# LED_Board_V2.net
KiCad netlist of a schematic drawn in EAGLE
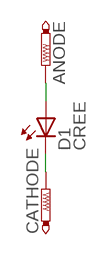
[diagram p0: schematic, sheet 1]

(export (version "E")
  (design (tool "Eeschema 10.0.6"))
  (components
    (comp (ref "ANODE")
      (value "PTR1PAD1-20")
      (footprint "eagle-import:P1-20")
      (libsource (lib "eagle-import") (part "PTR1PAD1-20"))
    )
    (comp (ref "CATHODE")
      (value "PTR1PAD1-20")
      (footprint "eagle-import:P1-20")
      (libsource (lib "eagle-import") (part "PTR1PAD1-20"))
    )
    (comp (ref "D1")
      (value "CREE")
      (footprint "eagle-import:CREE-XLAMP-XM-L")
      (libsource (lib "eagle-import") (part "CREE"))
    )
  )
  (nets
    (net (code "1") (name "Net-(ANODE-PadTP)") (class "Default")
      (node (ref "ANODE") (pin "TP") (pinfunction "TP_TP") (pintype "input"))
      (node (ref "D1") (pin "A") (pinfunction "A_A") (pintype "input"))
      (node (ref "D1") (pin "A@1") (pinfunction "A_A@1") (pintype "input"))
    )
    (net (code "2") (name "Net-(CATHODE-PadTP)") (class "Default")
      (node (ref "CATHODE") (pin "TP") (pinfunction "TP_TP") (pintype "input"))
      (node (ref "D1") (pin "C") (pinfunction "C_C") (pintype "output"))
      (node (ref "D1") (pin "C1") (pinfunction "C_C1") (pintype "output"))
      (node (ref "D1") (pin "C@1") (pinfunction "C_C@1") (pintype "output"))
    )
  )
)
